# untitled.net
KiCad netlist of a schematic drawn in EAGLE
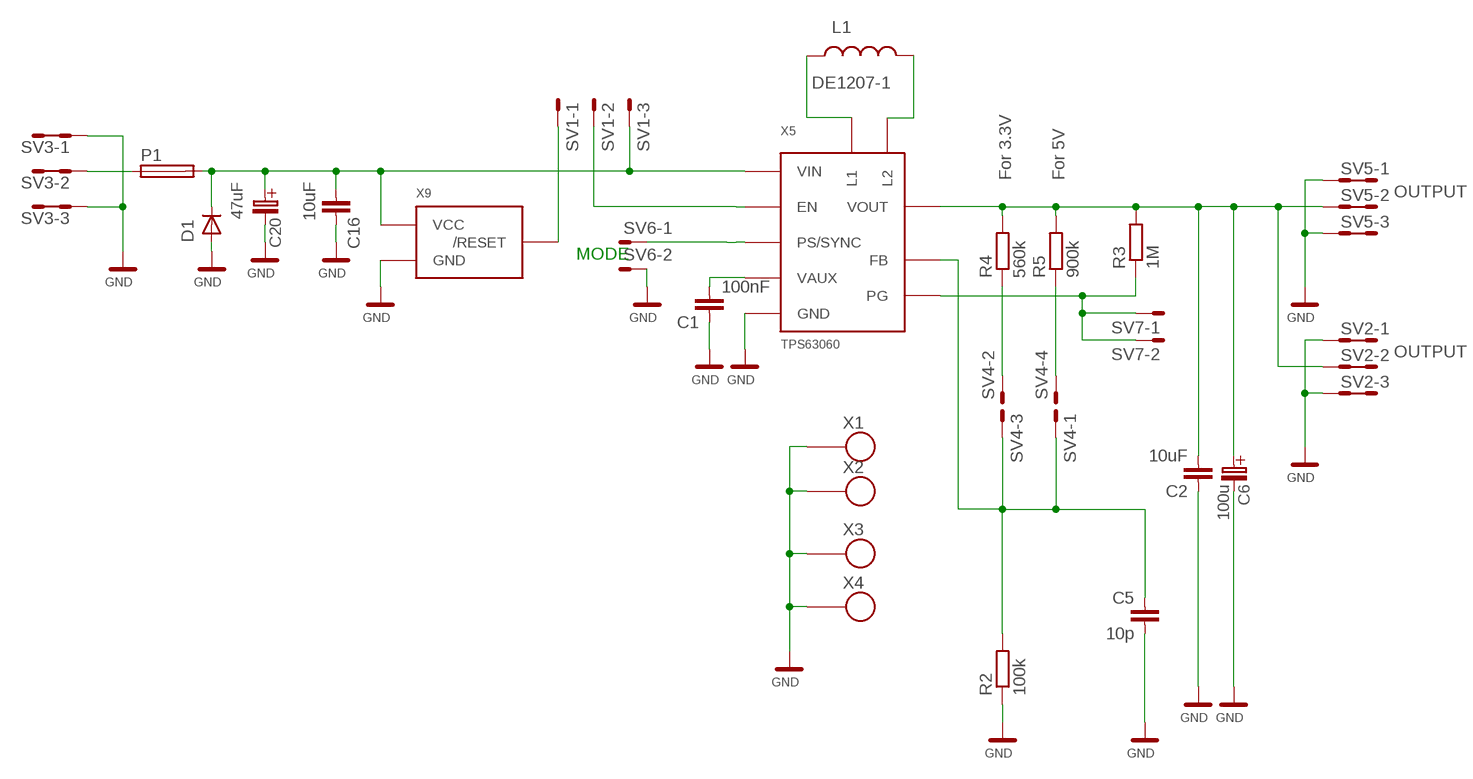
[diagram p0: schematic, sheet 1]

(export (version "E")
  (design (tool "Eeschema 10.0.6"))
  (components
    (comp (ref "C1")
      (value "100nF")
      (footprint "eagle-import:C0805")
      (libsource (lib "eagle-import") (part "C0805"))
    )
    (comp (ref "C2")
      (value "10uF")
      (footprint "eagle-import:C0805")
      (libsource (lib "eagle-import") (part "C0805"))
    )
    (comp (ref "C5")
      (value "10p")
      (footprint "eagle-import:C0805")
      (libsource (lib "eagle-import") (part "C0805"))
    )
    (comp (ref "C6") (value "100u") (footprint "eagle-import:C") (libsource (lib "eagle-import") (part "C")))
    (comp (ref "C16")
      (value "10uF")
      (footprint "eagle-import:C0805")
      (libsource (lib "eagle-import") (part "C0805"))
    )
    (comp (ref "C20") (value "47uF") (footprint "eagle-import:B") (libsource (lib "eagle-import") (part "B")))
    (comp (ref "D1")
      (value "D-OB.SMA")
      (footprint "eagle-import:SMA")
      (libsource (lib "eagle-import") (part "D-OB.SMA"))
    )
    (comp (ref "L1")
      (value "DE1207-1")
      (footprint "eagle-import:DE1205-10")
      (libsource (lib "eagle-import") (part "DE1205-10"))
    )
    (comp (ref "P1")
      (value "POJISTKA_1812")
      (footprint "eagle-import:1812")
      (libsource (lib "eagle-import") (part "POJISTKA_1812"))
    )
    (comp (ref "R2")
      (value "100k")
      (footprint "eagle-import:0805")
      (libsource (lib "eagle-import") (part "R0805"))
    )
    (comp (ref "R3")
      (value "1M")
      (footprint "eagle-import:0805")
      (libsource (lib "eagle-import") (part "R0805"))
    )
    (comp (ref "R4")
      (value "560k")
      (footprint "eagle-import:0805")
      (libsource (lib "eagle-import") (part "R0805"))
    )
    (comp (ref "R5")
      (value "900k")
      (footprint "eagle-import:0805")
      (libsource (lib "eagle-import") (part "R0805"))
    )
    (comp (ref "SV1")
      (value "MA03-1")
      (footprint "eagle-import:MA03-1")
      (libsource (lib "eagle-import") (part "MA03-1"))
    )
    (comp (ref "SV2")
      (value "MA03-2")
      (footprint "eagle-import:MA03-2")
      (libsource (lib "eagle-import") (part "MA03-2"))
    )
    (comp (ref "SV3")
      (value "MA03-2")
      (footprint "eagle-import:MA03-2")
      (libsource (lib "eagle-import") (part "MA03-2"))
    )
    (comp (ref "SV4")
      (value "MA02-3")
      (footprint "eagle-import:MA02-2")
      (libsource (lib "eagle-import") (part "MA02-3"))
    )
    (comp (ref "SV5")
      (value "MA03-2")
      (footprint "eagle-import:MA03-2")
      (libsource (lib "eagle-import") (part "MA03-2"))
    )
    (comp (ref "SV6")
      (value "MA02-1")
      (footprint "eagle-import:MA02-1")
      (libsource (lib "eagle-import") (part "MA02-1"))
    )
    (comp (ref "SV7")
      (value "MA02-1")
      (footprint "eagle-import:MA02-1")
      (libsource (lib "eagle-import") (part "MA02-1"))
    )
    (comp (ref "X1")
      (value "SROUB3M")
      (footprint "eagle-import:SROUB3M")
      (libsource (lib "eagle-import") (part "SROUB3M"))
    )
    (comp (ref "X2")
      (value "SROUB3M")
      (footprint "eagle-import:SROUB3M")
      (libsource (lib "eagle-import") (part "SROUB3M"))
    )
    (comp (ref "X3")
      (value "SROUB3M")
      (footprint "eagle-import:SROUB3M")
      (libsource (lib "eagle-import") (part "SROUB3M"))
    )
    (comp (ref "X4")
      (value "SROUB3M")
      (footprint "eagle-import:SROUB3M")
      (libsource (lib "eagle-import") (part "SROUB3M"))
    )
    (comp (ref "X5")
      (value "TPS63060")
      (footprint "eagle-import:SON10")
      (libsource (lib "eagle-import") (part "TPS63060"))
    )
    (comp (ref "X9")
      (value "APX809-26SA")
      (footprint "eagle-import:SOT23")
      (libsource (lib "eagle-import") (part "APX809-26SA"))
    )
  )
  (nets
    (net (code "1") (name "GND") (class "Default")
      (node (ref "C1") (pin "1") (pinfunction "1_1") (pintype "passive"))
      (node (ref "C16") (pin "1") (pinfunction "1_1") (pintype "passive"))
      (node (ref "C2") (pin "1") (pinfunction "1_1") (pintype "passive"))
      (node (ref "C20") (pin "-") (pinfunction "C_EL-_-") (pintype "passive"))
      (node (ref "C5") (pin "2") (pinfunction "2_2") (pintype "passive"))
      (node (ref "C6") (pin "-") (pinfunction "C_EL-_-") (pintype "passive"))
      (node (ref "D1") (pin "A") (pinfunction "A_A") (pintype "passive"))
      (node (ref "R2") (pin "1") (pinfunction "1_1") (pintype "passive"))
      (node (ref "SV2") (pin "1") (pinfunction "K_1") (pintype "passive"))
      (node (ref "SV2") (pin "2") (pinfunction "K_2") (pintype "passive"))
      (node (ref "SV2") (pin "5") (pinfunction "K_5") (pintype "passive"))
      (node (ref "SV2") (pin "6") (pinfunction "K_6") (pintype "passive"))
      (node (ref "SV3") (pin "1") (pinfunction "K_1") (pintype "passive"))
      (node (ref "SV3") (pin "2") (pinfunction "K_2") (pintype "passive"))
      (node (ref "SV3") (pin "5") (pinfunction "K_5") (pintype "passive"))
      (node (ref "SV3") (pin "6") (pinfunction "K_6") (pintype "passive"))
      (node (ref "SV5") (pin "1") (pinfunction "K_1") (pintype "passive"))
      (node (ref "SV5") (pin "2") (pinfunction "K_2") (pintype "passive"))
      (node (ref "SV5") (pin "5") (pinfunction "K_5") (pintype "passive"))
      (node (ref "SV5") (pin "6") (pinfunction "K_6") (pintype "passive"))
      (node (ref "SV6") (pin "2") (pinfunction "P$1_2") (pintype "passive"))
      (node (ref "X1") (pin "P$1") (pinfunction "P$1_P$1") (pintype "bidirectional"))
      (node (ref "X2") (pin "P$1") (pinfunction "P$1_P$1") (pintype "bidirectional"))
      (node (ref "X3") (pin "P$1") (pinfunction "P$1_P$1") (pintype "bidirectional"))
      (node (ref "X4") (pin "P$1") (pinfunction "P$1_P$1") (pintype "bidirectional"))
      (node (ref "X5") (pin "11") (pinfunction "GND_11") (pintype "passive"))
      (node (ref "X5") (pin "12") (pinfunction "GND_12") (pintype "passive"))
      (node (ref "X5") (pin "13") (pinfunction "GND_13") (pintype "passive"))
      (node (ref "X5") (pin "14") (pinfunction "GND_14") (pintype "passive"))
      (node (ref "X5") (pin "15") (pinfunction "GND_15") (pintype "passive"))
      (node (ref "X5") (pin "16") (pinfunction "GND_16") (pintype "passive"))
      (node (ref "X5") (pin "17") (pinfunction "GND_17") (pintype "passive"))
      (node (ref "X5") (pin "18") (pinfunction "GND_18") (pintype "passive"))
      (node (ref "X5") (pin "19") (pinfunction "GND_19") (pintype "passive"))
      (node (ref "X5") (pin "7") (pinfunction "GND_7") (pintype "passive"))
      (node (ref "X5") (pin "P$1") (pinfunction "GND_P$1") (pintype "passive"))
      (node (ref "X5") (pin "P$2") (pinfunction "GND_P$2") (pintype "passive"))
      (node (ref "X5") (pin "P$3") (pinfunction "GND_P$3") (pintype "passive"))
      (node (ref "X5") (pin "P$4") (pinfunction "GND_P$4") (pintype "passive"))
      (node (ref "X5") (pin "P$5") (pinfunction "GND_P$5") (pintype "passive"))
      (node (ref "X9") (pin "1") (pinfunction "GND_1") (pintype "passive"))
    )
    (net (code "2") (name "Net-(C6-C_EL+)") (class "Default")
      (node (ref "C2") (pin "2") (pinfunction "2_2") (pintype "passive"))
      (node (ref "C6") (pin "+") (pinfunction "C_EL+_+") (pintype "passive"))
      (node (ref "R3") (pin "2") (pinfunction "2_2") (pintype "passive"))
      (node (ref "R4") (pin "2") (pinfunction "2_2") (pintype "passive"))
      (node (ref "R5") (pin "2") (pinfunction "2_2") (pintype "passive"))
      (node (ref "SV2") (pin "3") (pinfunction "K_3") (pintype "passive"))
      (node (ref "SV2") (pin "4") (pinfunction "K_4") (pintype "passive"))
      (node (ref "SV5") (pin "3") (pinfunction "K_3") (pintype "passive"))
      (node (ref "SV5") (pin "4") (pinfunction "K_4") (pintype "passive"))
      (node (ref "X5") (pin "9") (pinfunction "VOUT_9") (pintype "output"))
    )
    (net (code "3") (name "Net-(C20-C_EL+)") (class "Default")
      (node (ref "C16") (pin "2") (pinfunction "2_2") (pintype "passive"))
      (node (ref "C20") (pin "+") (pinfunction "C_EL+_+") (pintype "passive"))
      (node (ref "D1") (pin "K") (pinfunction "C_K") (pintype "passive"))
      (node (ref "P1") (pin "2") (pinfunction "2_2") (pintype "passive"))
      (node (ref "SV1") (pin "3") (pinfunction "P$1_3") (pintype "passive"))
      (node (ref "X5") (pin "2") (pinfunction "VIN_2") (pintype "input"))
      (node (ref "X9") (pin "3") (pinfunction "VCC_3") (pintype "input"))
    )
    (net (code "4") (name "Net-(L1-1)") (class "Default")
      (node (ref "L1") (pin "P$1") (pinfunction "1_P$1") (pintype "passive"))
      (node (ref "X5") (pin "1") (pinfunction "L1_1") (pintype "passive"))
    )
    (net (code "5") (name "Net-(L1-2)") (class "Default")
      (node (ref "L1") (pin "P$2") (pinfunction "2_P$2") (pintype "passive"))
      (node (ref "X5") (pin "10") (pinfunction "L2_10") (pintype "passive"))
    )
    (net (code "6") (name "Net-(P1-Pad1)") (class "Default")
      (node (ref "P1") (pin "1") (pinfunction "1_1") (pintype "passive"))
      (node (ref "SV3") (pin "3") (pinfunction "K_3") (pintype "passive"))
      (node (ref "SV3") (pin "4") (pinfunction "K_4") (pintype "passive"))
    )
    (net (code "7") (name "Net-(SV1A-P$1)") (class "Default")
      (node (ref "SV1") (pin "1") (pinfunction "P$1_1") (pintype "passive"))
      (node (ref "X9") (pin "2") (pinfunction "/RESET_2") (pintype "passive"))
    )
    (net (code "8") (name "Net-(SV1B-P$1)") (class "Default")
      (node (ref "SV1") (pin "2") (pinfunction "P$1_2") (pintype "passive"))
      (node (ref "X5") (pin "3") (pinfunction "EN_3") (pintype "input"))
    )
    (net (code "9") (name "Net-(SV4A-P$1)") (class "Default")
      (node (ref "C5") (pin "1") (pinfunction "1_1") (pintype "passive"))
      (node (ref "R2") (pin "2") (pinfunction "2_2") (pintype "passive"))
      (node (ref "SV4") (pin "1") (pinfunction "P$1_1") (pintype "passive"))
      (node (ref "SV4") (pin "3") (pinfunction "P$1_3") (pintype "passive"))
      (node (ref "X5") (pin "8") (pinfunction "FB_8") (pintype "input"))
    )
    (net (code "10") (name "Net-(SV4B-P$1)") (class "Default")
      (node (ref "R4") (pin "1") (pinfunction "1_1") (pintype "passive"))
      (node (ref "SV4") (pin "2") (pinfunction "P$1_2") (pintype "passive"))
    )
    (net (code "11") (name "Net-(SV4D-P$1)") (class "Default")
      (node (ref "R5") (pin "1") (pinfunction "1_1") (pintype "passive"))
      (node (ref "SV4") (pin "4") (pinfunction "P$1_4") (pintype "passive"))
    )
    (net (code "12") (name "Net-(SV6A-P$1)") (class "Default")
      (node (ref "SV6") (pin "1") (pinfunction "P$1_1") (pintype "passive"))
      (node (ref "X5") (pin "4") (pinfunction "PS/SYNC_4") (pintype "input"))
    )
    (net (code "13") (name "Net-(SV7A-P$1)") (class "Default")
      (node (ref "R3") (pin "1") (pinfunction "1_1") (pintype "passive"))
      (node (ref "SV7") (pin "1") (pinfunction "P$1_1") (pintype "passive"))
      (node (ref "SV7") (pin "2") (pinfunction "P$1_2") (pintype "passive"))
      (node (ref "X5") (pin "5") (pinfunction "PG_5") (pintype "input"))
    )
    (net (code "14") (name "Net-(X5-VAUX)") (class "Default")
      (node (ref "C1") (pin "2") (pinfunction "2_2") (pintype "passive"))
      (node (ref "X5") (pin "6") (pinfunction "VAUX_6") (pintype "input"))
    )
  )
)
